# Sheet1.net
KiCad netlist of a schematic drawn in Altium Designer
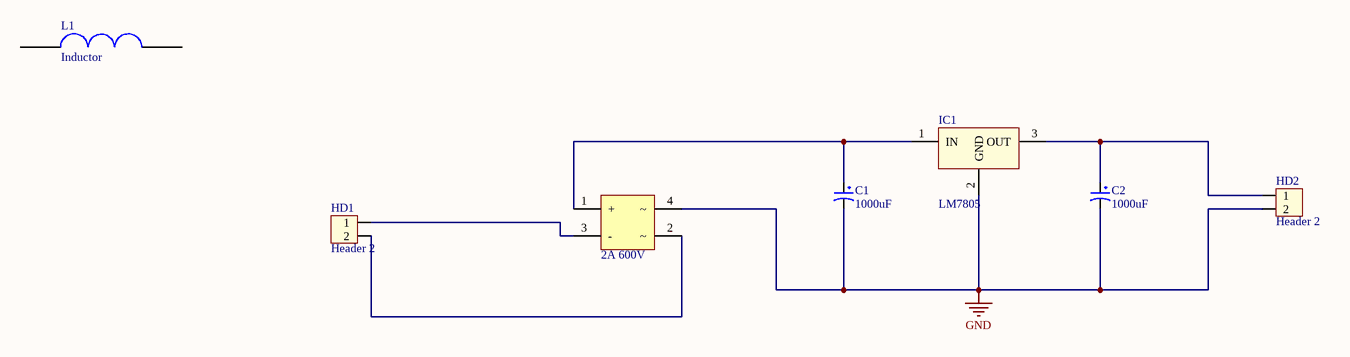
[diagram p0: Sheet1.SchDoc]

(export (version "E")
  (design (tool "Eeschema 10.0.6"))
  (components
    (comp (ref "C1")
      (value "1000uF")
      (footprint "tu hoa 13mm")
      (description "Cắm")
      (libsource (lib "Tu dien") (part "Tu Hoa 1000uF 50V 13x26"))
    )
    (comp (ref "C2")
      (value "1000uF")
      (footprint "tu hoa 13mm")
      (description "Cắm")
      (libsource (lib "Tu dien") (part "Tu Hoa 1000uF 50V 13x26"))
    )
    (comp (ref "D1")
      (value "2A 600V")
      (footprint "DIODE CAU 2A 3A CAM")
      (description "Cắm")
      (libsource (lib "Diode") (part "Diode CAU 2A VUONG"))
    )
    (comp (ref "HD1")
      (value "Header 2")
      (footprint "HED2")
      (description "Header 2 (Green)")
      (libsource (lib "") (part "Hed2_1"))
    )
    (comp (ref "HD2")
      (value "Header 2")
      (footprint "HED2")
      (description "Header 2 (Green)")
      (libsource (lib "KhanhBK_SCH_Library_2") (part "Hed2"))
    )
    (comp (ref "IC1")
      (value "LM7805")
      (footprint "QTO-220")
      (description "On ap +, from + 5 to + 24VDC")
      (libsource (lib "KhanhBK_SCH_Library_2") (part "LM78xx"))
    )
    (comp (ref "L1")
      (value "Inductor")
      (footprint "Inductor")
      (libsource (lib "my library") (part "Inductor"))
    )
  )
  (nets
    (net (code "1") (name "GND") (class "Default")
      (node (ref "C1") (pin "2") (pinfunction "2_2") (pintype "passive"))
      (node (ref "C2") (pin "2") (pinfunction "2_2") (pintype "passive"))
      (node (ref "D1") (pin "4") (pinfunction "~_4") (pintype "passive"))
      (node (ref "HD2") (pin "2") (pinfunction "2_2") (pintype "passive"))
      (node (ref "IC1") (pin "2") (pinfunction "GND_2") (pintype "passive"))
    )
    (net (code "2") (name "Net-(D1-+)") (class "Default")
      (node (ref "C1") (pin "1") (pinfunction "1_1") (pintype "passive"))
      (node (ref "D1") (pin "1") (pinfunction "+_1") (pintype "passive"))
      (node (ref "IC1") (pin "1") (pinfunction "IN_1") (pintype "passive"))
    )
    (net (code "3") (name "Net-(D1--)") (class "Default")
      (node (ref "D1") (pin "3") (pinfunction "-_3") (pintype "passive"))
      (node (ref "HD1") (pin "1") (pinfunction "1_1") (pintype "passive"))
    )
    (net (code "4") (name "Net-(D1-~-Pad2)") (class "Default")
      (node (ref "D1") (pin "2") (pinfunction "~_2") (pintype "passive"))
      (node (ref "HD1") (pin "2") (pinfunction "2_2") (pintype "passive"))
    )
    (net (code "5") (name "Net-(IC1-OUT)") (class "Default")
      (node (ref "C2") (pin "1") (pinfunction "1_1") (pintype "passive"))
      (node (ref "HD2") (pin "1") (pinfunction "1_1") (pintype "passive"))
      (node (ref "IC1") (pin "3") (pinfunction "OUT_3") (pintype "passive"))
    )
    (net (code "6") (name "unconnected-(L1-Pad1)") (class "Default")
      (node (ref "L1") (pin "1") (pinfunction "1_1") (pintype "passive"))
    )
    (net (code "7") (name "unconnected-(L1-Pad2)") (class "Default")
      (node (ref "L1") (pin "2") (pinfunction "2_2") (pintype "passive"))
    )
  )
)
